# front_module_3.net
KiCad netlist of a schematic drawn in EAGLE
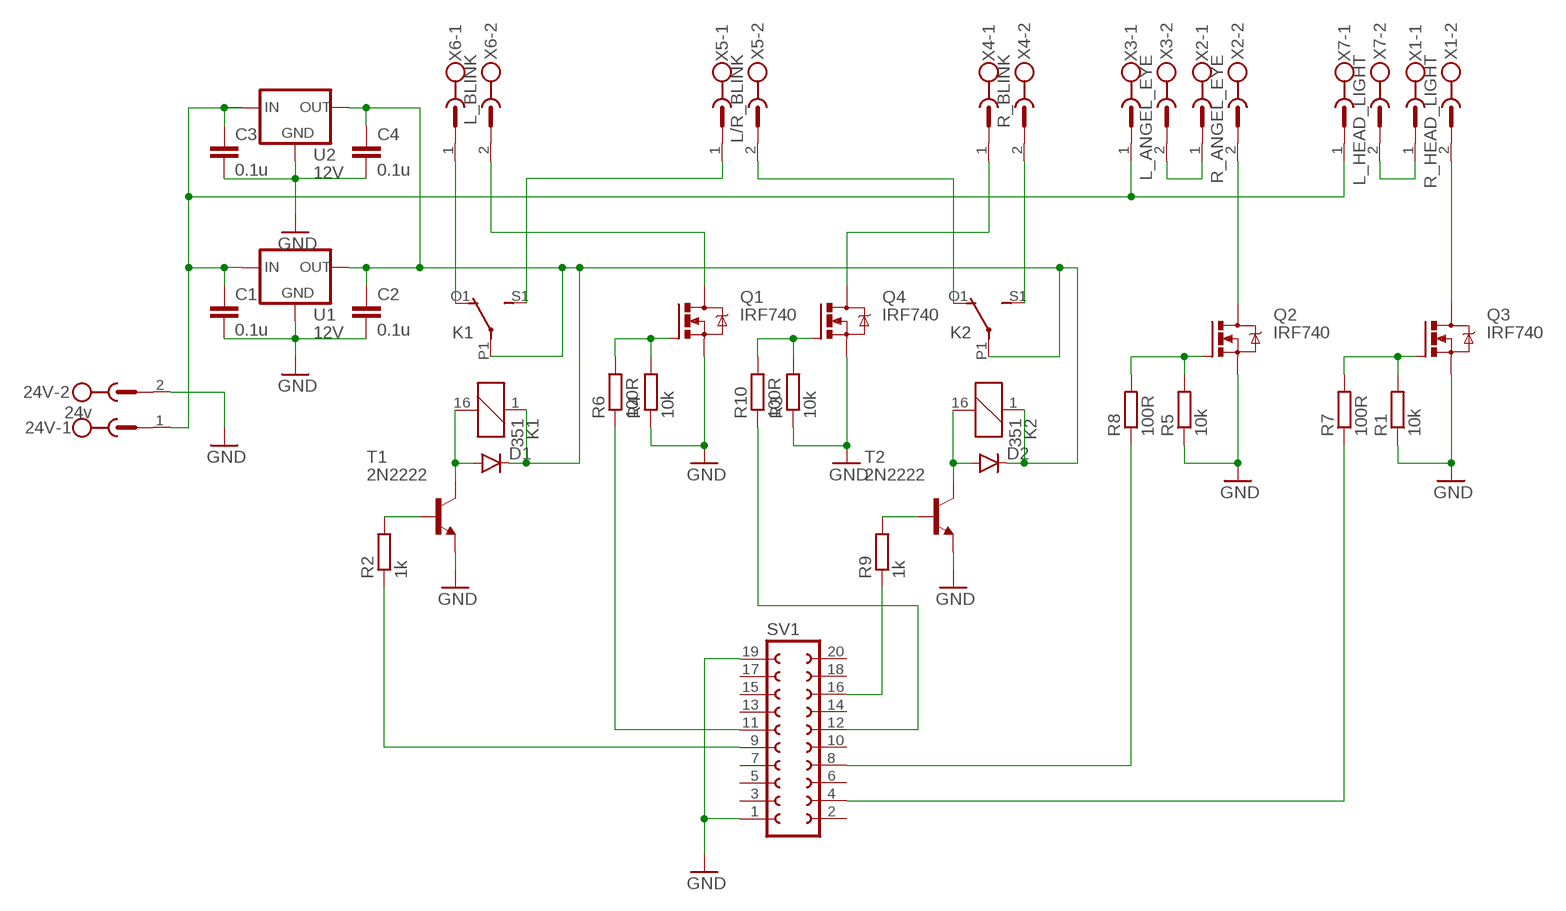
[diagram p0: schematic, sheet 1]

(export (version "E")
  (design (tool "Eeschema 10.0.6"))
  (components
    (comp (ref "24V")
      (value "24v")
      (footprint "eagle-import:MSTBV2")
      (libsource (lib "eagle-import") (part "MSTBV2"))
    )
    (comp (ref "C1")
      (value "0.1u")
      (footprint "eagle-import:CAP-PTH-SMALL-KIT")
      (libsource (lib "eagle-import") (part "0.1UF-50V-20%(PTH)KIT-EZ"))
    )
    (comp (ref "C2")
      (value "0.1u")
      (footprint "eagle-import:CAP-PTH-SMALL-KIT")
      (libsource (lib "eagle-import") (part "0.1UF-50V-20%(PTH)KIT-EZ"))
    )
    (comp (ref "C3")
      (value "0.1u")
      (footprint "eagle-import:CAP-PTH-SMALL-KIT")
      (libsource (lib "eagle-import") (part "0.1UF-50V-20%(PTH)KIT-EZ"))
    )
    (comp (ref "C4")
      (value "0.1u")
      (footprint "eagle-import:CAP-PTH-SMALL-KIT")
      (libsource (lib "eagle-import") (part "0.1UF-50V-20%(PTH)KIT-EZ"))
    )
    (comp (ref "D1")
      (value "DIODEKIT2")
      (footprint "eagle-import:DIODE-1N4001-KIT")
      (libsource (lib "eagle-import") (part "DIODEKIT2"))
    )
    (comp (ref "D2")
      (value "DIODEKIT2")
      (footprint "eagle-import:DIODE-1N4001-KIT")
      (libsource (lib "eagle-import") (part "DIODEKIT2"))
    )
    (comp (ref "K1")
      (value "351")
      (footprint "eagle-import:351")
      (libsource (lib "eagle-import") (part "351"))
    )
    (comp (ref "K2")
      (value "351")
      (footprint "eagle-import:351")
      (libsource (lib "eagle-import") (part "351"))
    )
    (comp (ref "Q1")
      (value "IRF740")
      (footprint "eagle-import:TO220BV")
      (libsource (lib "eagle-import") (part "IRF740"))
    )
    (comp (ref "Q2")
      (value "IRF740")
      (footprint "eagle-import:TO220BV")
      (libsource (lib "eagle-import") (part "IRF740"))
    )
    (comp (ref "Q3")
      (value "IRF740")
      (footprint "eagle-import:TO220BV")
      (libsource (lib "eagle-import") (part "IRF740"))
    )
    (comp (ref "Q4")
      (value "IRF740")
      (footprint "eagle-import:TO220BV")
      (libsource (lib "eagle-import") (part "IRF740"))
    )
    (comp (ref "R1")
      (value "10k")
      (footprint "eagle-import:0207_10")
      (libsource (lib "eagle-import") (part "R-EU_0207/10"))
    )
    (comp (ref "R2")
      (value "1k")
      (footprint "eagle-import:0207_10")
      (libsource (lib "eagle-import") (part "R-EU_0207/10"))
    )
    (comp (ref "R3")
      (value "10k")
      (footprint "eagle-import:0207_10")
      (libsource (lib "eagle-import") (part "R-EU_0207/10"))
    )
    (comp (ref "R4")
      (value "10k")
      (footprint "eagle-import:0207_10")
      (libsource (lib "eagle-import") (part "R-EU_0207/10"))
    )
    (comp (ref "R5")
      (value "10k")
      (footprint "eagle-import:0207_10")
      (libsource (lib "eagle-import") (part "R-EU_0207/10"))
    )
    (comp (ref "R6")
      (value "100R")
      (footprint "eagle-import:0207_10")
      (libsource (lib "eagle-import") (part "R-EU_0207/10"))
    )
    (comp (ref "R7")
      (value "100R")
      (footprint "eagle-import:0207_10")
      (libsource (lib "eagle-import") (part "R-EU_0207/10"))
    )
    (comp (ref "R8")
      (value "100R")
      (footprint "eagle-import:0207_10")
      (libsource (lib "eagle-import") (part "R-EU_0207/10"))
    )
    (comp (ref "R9")
      (value "1k")
      (footprint "eagle-import:0207_10")
      (libsource (lib "eagle-import") (part "R-EU_0207/10"))
    )
    (comp (ref "R10")
      (value "100R")
      (footprint "eagle-import:0207_10")
      (libsource (lib "eagle-import") (part "R-EU_0207/10"))
    )
    (comp (ref "SV1")
      (value "FE10-2W")
      (footprint "eagle-import:FE10-2W")
      (libsource (lib "eagle-import") (part "FE10-2W"))
    )
    (comp (ref "T1")
      (value "2N2222")
      (footprint "eagle-import:TO92-EBC-OVAL")
      (libsource (lib "eagle-import") (part "2N2222"))
    )
    (comp (ref "T2")
      (value "2N2222")
      (footprint "eagle-import:TO92-EBC-OVAL")
      (libsource (lib "eagle-import") (part "2N2222"))
    )
    (comp (ref "U1")
      (value "12V")
      (footprint "eagle-import:TO220-IGO")
      (libsource (lib "eagle-import") (part "V_REG_78XXSINK"))
    )
    (comp (ref "U2")
      (value "12V")
      (footprint "eagle-import:TO220-IGO")
      (libsource (lib "eagle-import") (part "V_REG_78XXSINK"))
    )
    (comp (ref "X1")
      (value "R_HEAD_LIGHT")
      (footprint "eagle-import:MSTBV2")
      (libsource (lib "eagle-import") (part "MSTBV2"))
    )
    (comp (ref "X2")
      (value "R_ANGEL_EYE")
      (footprint "eagle-import:MSTBV2")
      (libsource (lib "eagle-import") (part "MSTBV2"))
    )
    (comp (ref "X3")
      (value "L_ANGEL_EYE")
      (footprint "eagle-import:MSTBV2")
      (libsource (lib "eagle-import") (part "MSTBV2"))
    )
    (comp (ref "X4")
      (value "R_BLINK")
      (footprint "eagle-import:MSTBV2")
      (libsource (lib "eagle-import") (part "MSTBV2"))
    )
    (comp (ref "X5")
      (value "L/R_BLINK")
      (footprint "eagle-import:MSTBV2")
      (libsource (lib "eagle-import") (part "MSTBV2"))
    )
    (comp (ref "X6")
      (value "L_BLINK")
      (footprint "eagle-import:MSTBV2")
      (libsource (lib "eagle-import") (part "MSTBV2"))
    )
    (comp (ref "X7")
      (value "L_HEAD_LIGHT")
      (footprint "eagle-import:MSTBV2")
      (libsource (lib "eagle-import") (part "MSTBV2"))
    )
  )
  (nets
    (net (code "1") (name "GND") (class "Default")
      (node (ref "24V") (pin "2") (pinfunction "SK_2") (pintype "passive"))
      (node (ref "C1") (pin "2") (pinfunction "2_2") (pintype "passive"))
      (node (ref "C2") (pin "2") (pinfunction "2_2") (pintype "passive"))
      (node (ref "C3") (pin "2") (pinfunction "2_2") (pintype "passive"))
      (node (ref "C4") (pin "2") (pinfunction "2_2") (pintype "passive"))
      (node (ref "Q1") (pin "S") (pinfunction "S_S") (pintype "passive"))
      (node (ref "Q2") (pin "S") (pinfunction "S_S") (pintype "passive"))
      (node (ref "Q3") (pin "S") (pinfunction "S_S") (pintype "passive"))
      (node (ref "Q4") (pin "S") (pinfunction "S_S") (pintype "passive"))
      (node (ref "R1") (pin "1") (pinfunction "1_1") (pintype "passive"))
      (node (ref "R3") (pin "1") (pinfunction "1_1") (pintype "passive"))
      (node (ref "R4") (pin "1") (pinfunction "1_1") (pintype "passive"))
      (node (ref "R5") (pin "1") (pinfunction "1_1") (pintype "passive"))
      (node (ref "SV1") (pin "1") (pinfunction "1_1") (pintype "passive"))
      (node (ref "SV1") (pin "19") (pinfunction "19_19") (pintype "passive"))
      (node (ref "T1") (pin "E") (pinfunction "E_E") (pintype "passive"))
      (node (ref "T2") (pin "E") (pinfunction "E_E") (pintype "passive"))
      (node (ref "U1") (pin "GND") (pinfunction "GND_GND") (pintype "input"))
      (node (ref "U2") (pin "GND") (pinfunction "GND_GND") (pintype "input"))
    )
    (net (code "2") (name "Net-(24VA-SK)") (class "Default")
      (node (ref "24V") (pin "1") (pinfunction "SK_1") (pintype "passive"))
      (node (ref "C1") (pin "1") (pinfunction "1_1") (pintype "passive"))
      (node (ref "C3") (pin "1") (pinfunction "1_1") (pintype "passive"))
      (node (ref "U1") (pin "IN") (pinfunction "IN_IN") (pintype "input"))
      (node (ref "U2") (pin "IN") (pinfunction "IN_IN") (pintype "input"))
      (node (ref "X3") (pin "1") (pinfunction "SK_1") (pintype "passive"))
      (node (ref "X7") (pin "1") (pinfunction "SK_1") (pintype "passive"))
    )
    (net (code "3") (name "Net-(K1A-2)") (class "Default")
      (node (ref "D1") (pin "A") (pinfunction "A_A") (pintype "passive"))
      (node (ref "K1") (pin "16") (pinfunction "2_16") (pintype "passive"))
      (node (ref "T1") (pin "C") (pinfunction "C_C") (pintype "passive"))
    )
    (net (code "4") (name "Net-(K1B-O)") (class "Default")
      (node (ref "K1") (pin "O1") (pinfunction "O_O1") (pintype "passive"))
      (node (ref "X6") (pin "1") (pinfunction "SK_1") (pintype "passive"))
    )
    (net (code "5") (name "Net-(K1B-P)") (class "Default")
      (node (ref "C2") (pin "1") (pinfunction "1_1") (pintype "passive"))
      (node (ref "C4") (pin "1") (pinfunction "1_1") (pintype "passive"))
      (node (ref "D1") (pin "C") (pinfunction "C_C") (pintype "passive"))
      (node (ref "D2") (pin "C") (pinfunction "C_C") (pintype "passive"))
      (node (ref "K1") (pin "1") (pinfunction "1_1") (pintype "passive"))
      (node (ref "K1") (pin "P1") (pinfunction "P_P1") (pintype "passive"))
      (node (ref "K2") (pin "1") (pinfunction "1_1") (pintype "passive"))
      (node (ref "K2") (pin "P1") (pinfunction "P_P1") (pintype "passive"))
      (node (ref "U1") (pin "OUT") (pinfunction "OUT_OUT") (pintype "output"))
      (node (ref "U2") (pin "OUT") (pinfunction "OUT_OUT") (pintype "output"))
    )
    (net (code "6") (name "Net-(K1B-S)") (class "Default")
      (node (ref "K1") (pin "S1") (pinfunction "S_S1") (pintype "passive"))
      (node (ref "X5") (pin "1") (pinfunction "SK_1") (pintype "passive"))
    )
    (net (code "7") (name "Net-(K2A-2)") (class "Default")
      (node (ref "D2") (pin "A") (pinfunction "A_A") (pintype "passive"))
      (node (ref "K2") (pin "16") (pinfunction "2_16") (pintype "passive"))
      (node (ref "T2") (pin "C") (pinfunction "C_C") (pintype "passive"))
    )
    (net (code "8") (name "Net-(K2B-O)") (class "Default")
      (node (ref "K2") (pin "O1") (pinfunction "O_O1") (pintype "passive"))
      (node (ref "X5") (pin "2") (pinfunction "SK_2") (pintype "passive"))
    )
    (net (code "9") (name "Net-(K2B-S)") (class "Default")
      (node (ref "K2") (pin "S1") (pinfunction "S_S1") (pintype "passive"))
      (node (ref "X4") (pin "2") (pinfunction "SK_2") (pintype "passive"))
    )
    (net (code "10") (name "Net-(Q1-PadG)") (class "Default")
      (node (ref "Q1") (pin "G") (pinfunction "G_G") (pintype "passive"))
      (node (ref "R4") (pin "2") (pinfunction "2_2") (pintype "passive"))
      (node (ref "R6") (pin "2") (pinfunction "2_2") (pintype "passive"))
    )
    (net (code "11") (name "Net-(Q2-PadG)") (class "Default")
      (node (ref "Q2") (pin "G") (pinfunction "G_G") (pintype "passive"))
      (node (ref "R5") (pin "2") (pinfunction "2_2") (pintype "passive"))
      (node (ref "R8") (pin "2") (pinfunction "2_2") (pintype "passive"))
    )
    (net (code "12") (name "Net-(Q3-PadG)") (class "Default")
      (node (ref "Q3") (pin "G") (pinfunction "G_G") (pintype "passive"))
      (node (ref "R1") (pin "2") (pinfunction "2_2") (pintype "passive"))
      (node (ref "R7") (pin "2") (pinfunction "2_2") (pintype "passive"))
    )
    (net (code "13") (name "Net-(Q4-PadG)") (class "Default")
      (node (ref "Q4") (pin "G") (pinfunction "G_G") (pintype "passive"))
      (node (ref "R10") (pin "2") (pinfunction "2_2") (pintype "passive"))
      (node (ref "R3") (pin "2") (pinfunction "2_2") (pintype "passive"))
    )
    (net (code "14") (name "Net-(R2-Pad1)") (class "Default")
      (node (ref "R2") (pin "1") (pinfunction "1_1") (pintype "passive"))
      (node (ref "SV1") (pin "9") (pinfunction "9_9") (pintype "passive"))
    )
    (net (code "15") (name "Net-(R2-Pad2)") (class "Default")
      (node (ref "R2") (pin "2") (pinfunction "2_2") (pintype "passive"))
      (node (ref "T1") (pin "B") (pinfunction "B_B") (pintype "passive"))
    )
    (net (code "16") (name "Net-(R6-Pad1)") (class "Default")
      (node (ref "R6") (pin "1") (pinfunction "1_1") (pintype "passive"))
      (node (ref "SV1") (pin "11") (pinfunction "11_11") (pintype "passive"))
    )
    (net (code "17") (name "Net-(R7-Pad1)") (class "Default")
      (node (ref "R7") (pin "1") (pinfunction "1_1") (pintype "passive"))
      (node (ref "SV1") (pin "4") (pinfunction "4_4") (pintype "passive"))
    )
    (net (code "18") (name "Net-(R8-Pad1)") (class "Default")
      (node (ref "R8") (pin "1") (pinfunction "1_1") (pintype "passive"))
      (node (ref "SV1") (pin "8") (pinfunction "8_8") (pintype "passive"))
    )
    (net (code "19") (name "Net-(R9-Pad1)") (class "Default")
      (node (ref "R9") (pin "1") (pinfunction "1_1") (pintype "passive"))
      (node (ref "SV1") (pin "16") (pinfunction "16_16") (pintype "passive"))
    )
    (net (code "20") (name "Net-(R9-Pad2)") (class "Default")
      (node (ref "R9") (pin "2") (pinfunction "2_2") (pintype "passive"))
      (node (ref "T2") (pin "B") (pinfunction "B_B") (pintype "passive"))
    )
    (net (code "21") (name "Net-(R10-Pad1)") (class "Default")
      (node (ref "R10") (pin "1") (pinfunction "1_1") (pintype "passive"))
      (node (ref "SV1") (pin "12") (pinfunction "12_12") (pintype "passive"))
    )
    (net (code "22") (name "Net-(X1A-SK)") (class "Default")
      (node (ref "X1") (pin "1") (pinfunction "SK_1") (pintype "passive"))
      (node (ref "X7") (pin "2") (pinfunction "SK_2") (pintype "passive"))
    )
    (net (code "23") (name "Net-(X1B-SK)") (class "Default")
      (node (ref "Q3") (pin "D") (pinfunction "D_D") (pintype "passive"))
      (node (ref "X1") (pin "2") (pinfunction "SK_2") (pintype "passive"))
    )
    (net (code "24") (name "Net-(X2A-SK)") (class "Default")
      (node (ref "X2") (pin "1") (pinfunction "SK_1") (pintype "passive"))
      (node (ref "X3") (pin "2") (pinfunction "SK_2") (pintype "passive"))
    )
    (net (code "25") (name "Net-(X2B-SK)") (class "Default")
      (node (ref "Q2") (pin "D") (pinfunction "D_D") (pintype "passive"))
      (node (ref "X2") (pin "2") (pinfunction "SK_2") (pintype "passive"))
    )
    (net (code "26") (name "Net-(X4A-SK)") (class "Default")
      (node (ref "Q4") (pin "D") (pinfunction "D_D") (pintype "passive"))
      (node (ref "X4") (pin "1") (pinfunction "SK_1") (pintype "passive"))
    )
    (net (code "27") (name "Net-(X6B-SK)") (class "Default")
      (node (ref "Q1") (pin "D") (pinfunction "D_D") (pintype "passive"))
      (node (ref "X6") (pin "2") (pinfunction "SK_2") (pintype "passive"))
    )
    (net (code "28") (name "unconnected-(SV1-Pad2)") (class "Default")
      (node (ref "SV1") (pin "2") (pinfunction "2_2") (pintype "passive"))
    )
    (net (code "29") (name "unconnected-(SV1-Pad3)") (class "Default")
      (node (ref "SV1") (pin "3") (pinfunction "3_3") (pintype "passive"))
    )
    (net (code "30") (name "unconnected-(SV1-Pad5)") (class "Default")
      (node (ref "SV1") (pin "5") (pinfunction "5_5") (pintype "passive"))
    )
    (net (code "31") (name "unconnected-(SV1-Pad6)") (class "Default")
      (node (ref "SV1") (pin "6") (pinfunction "6_6") (pintype "passive"))
    )
    (net (code "32") (name "unconnected-(SV1-Pad7)") (class "Default")
      (node (ref "SV1") (pin "7") (pinfunction "7_7") (pintype "passive"))
    )
    (net (code "33") (name "unconnected-(SV1-Pad10)") (class "Default")
      (node (ref "SV1") (pin "10") (pinfunction "10_10") (pintype "passive"))
    )
    (net (code "34") (name "unconnected-(SV1-Pad13)") (class "Default")
      (node (ref "SV1") (pin "13") (pinfunction "13_13") (pintype "passive"))
    )
    (net (code "35") (name "unconnected-(SV1-Pad14)") (class "Default")
      (node (ref "SV1") (pin "14") (pinfunction "14_14") (pintype "passive"))
    )
    (net (code "36") (name "unconnected-(SV1-Pad15)") (class "Default")
      (node (ref "SV1") (pin "15") (pinfunction "15_15") (pintype "passive"))
    )
    (net (code "37") (name "unconnected-(SV1-Pad17)") (class "Default")
      (node (ref "SV1") (pin "17") (pinfunction "17_17") (pintype "passive"))
    )
    (net (code "38") (name "unconnected-(SV1-Pad18)") (class "Default")
      (node (ref "SV1") (pin "18") (pinfunction "18_18") (pintype "passive"))
    )
    (net (code "39") (name "unconnected-(SV1-Pad20)") (class "Default")
      (node (ref "SV1") (pin "20") (pinfunction "20_20") (pintype "passive"))
    )
  )
)
